# RoboRoach.net
KiCad netlist of a schematic drawn in EAGLE
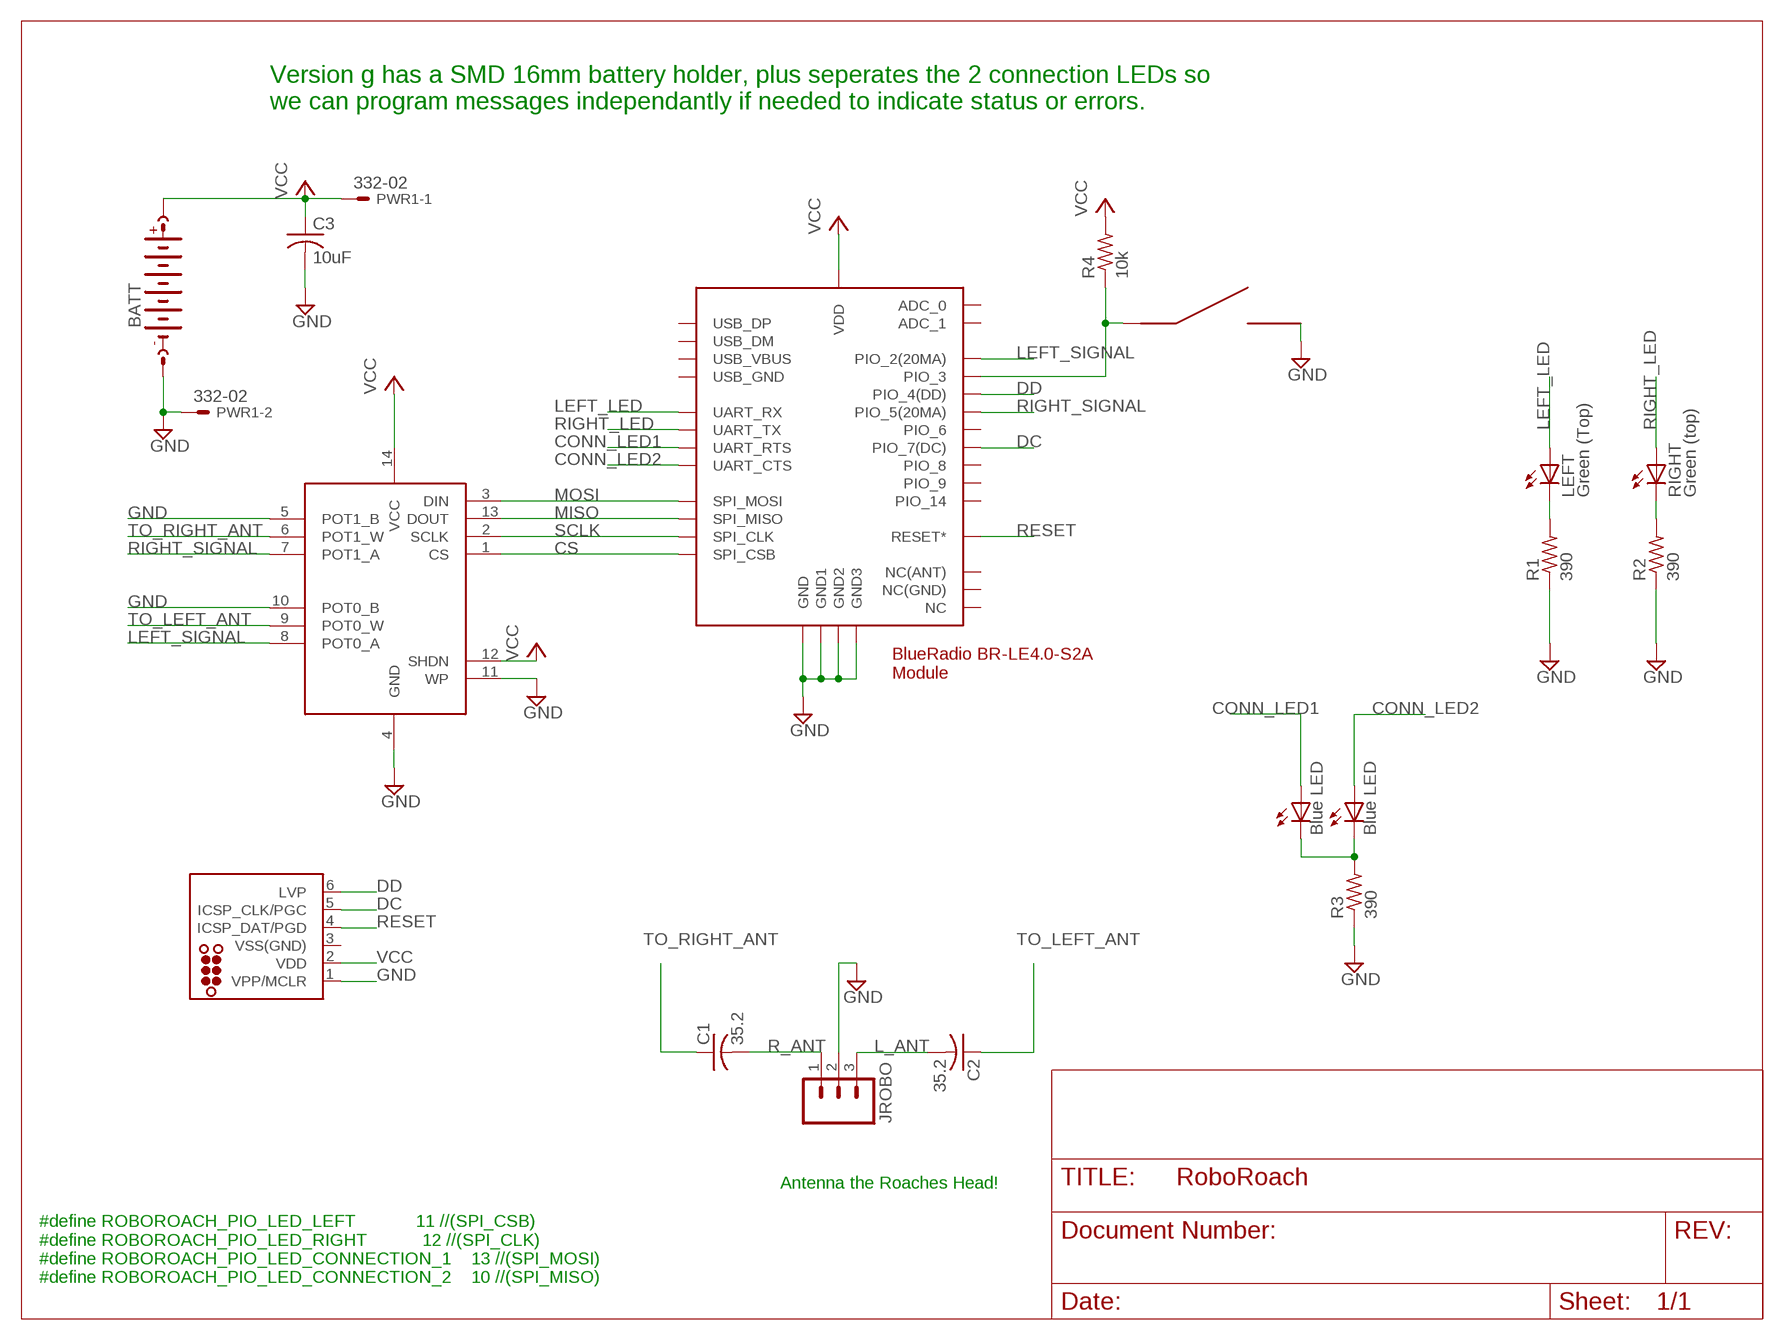
[diagram p0: schematic, sheet 1]

(export (version "E")
  (design (tool "Eeschema 10.0.6"))
  (components
    (comp (ref "BATT")
      (value "BATTERY-16MMSMD")
      (footprint "eagle-import:16M_BATT_SMD")
      (libsource (lib "eagle-import") (part "BATTERY-16MMSMD"))
    )
    (comp (ref "C1")
      (value "35.2")
      (footprint "eagle-import:C0805")
      (libsource (lib "eagle-import") (part "C-USC0805"))
    )
    (comp (ref "C2")
      (value "35.2")
      (footprint "eagle-import:C0805")
      (libsource (lib "eagle-import") (part "C-USC0805"))
    )
    (comp (ref "C3")
      (value "10uF")
      (footprint "eagle-import:C0805")
      (libsource (lib "eagle-import") (part "C-USC0805"))
    )
    (comp (ref "CONNECTION")
      (value "Blue LED")
      (footprint "eagle-import:CHIPLED_1206")
      (libsource (lib "eagle-import") (part "LEDCHIPLED_1206"))
    )
    (comp (ref "CONNECTION1")
      (value "Blue LED")
      (footprint "eagle-import:CHIPLED_1206")
      (libsource (lib "eagle-import") (part "LEDCHIPLED_1206"))
    )
    (comp (ref "IC1")
      (value "BR-LE4.0-S2")
      (footprint "eagle-import:BR-LE4.0-X2A")
      (libsource (lib "eagle-import") (part "BR-LE4.0-S2"))
    )
    (comp (ref "J1")
      (value "TC2030-MCP-NL")
      (footprint "eagle-import:TC2030-MCP-NL")
      (libsource (lib "eagle-import") (part "TC2030-MCP-NL"))
    )
    (comp (ref "JROBO")
      (value "M03PTH")
      (footprint "eagle-import:1X03")
      (libsource (lib "eagle-import") (part "M03PTH"))
    )
    (comp (ref "LEFT")
      (value "Green (Top)")
      (footprint "eagle-import:CHIPLED_1206")
      (libsource (lib "eagle-import") (part "LEDCHIPLED_1206"))
    )
    (comp (ref "POT")
      (value "MCP4251")
      (footprint "eagle-import:TSSOP14")
      (libsource (lib "eagle-import") (part "MCP4251"))
    )
    (comp (ref "PWR1")
      (value "332-02")
      (footprint "eagle-import:332-02")
      (libsource (lib "eagle-import") (part "332-02"))
    )
    (comp (ref "R1")
      (value "390")
      (footprint "eagle-import:R0805")
      (libsource (lib "eagle-import") (part "R-US_R0805"))
    )
    (comp (ref "R2")
      (value "390")
      (footprint "eagle-import:R0805")
      (libsource (lib "eagle-import") (part "R-US_R0805"))
    )
    (comp (ref "R3")
      (value "390")
      (footprint "eagle-import:R0805")
      (libsource (lib "eagle-import") (part "R-US_R0805"))
    )
    (comp (ref "R4")
      (value "10k")
      (footprint "eagle-import:R0805")
      (libsource (lib "eagle-import") (part "R-US_R0805"))
    )
    (comp (ref "RIGHT")
      (value "Green (top)")
      (footprint "eagle-import:CHIPLED_1206")
      (libsource (lib "eagle-import") (part "LEDCHIPLED_1206"))
    )
    (comp (ref "U$2")
      (value "B3U-1000X")
      (footprint "eagle-import:B3U")
      (libsource (lib "eagle-import") (part "B3U-1000X"))
    )
  )
  (nets
    (net (code "1") (name "/CONN_LED1") (class "Default")
      (node (ref "CONNECTION1") (pin "A") (pinfunction "A_A") (pintype "passive"))
      (node (ref "IC1") (pin "P$12") (pinfunction "UART_RTS_P$12") (pintype "bidirectional"))
    )
    (net (code "2") (name "/CONN_LED2") (class "Default")
      (node (ref "CONNECTION") (pin "A") (pinfunction "A_A") (pintype "passive"))
      (node (ref "IC1") (pin "P$11") (pinfunction "UART_CTS_P$11") (pintype "bidirectional"))
    )
    (net (code "3") (name "/CS") (class "Default")
      (node (ref "IC1") (pin "P$6") (pinfunction "SPI_CSB_P$6") (pintype "bidirectional"))
      (node (ref "POT") (pin "1") (pinfunction "CS_1") (pintype "input"))
    )
    (net (code "4") (name "/DC") (class "Default")
      (node (ref "IC1") (pin "P$29") (pinfunction "PIO_7(DC)_P$29") (pintype "bidirectional"))
      (node (ref "J1") (pin "5") (pinfunction "ICSP_CLK/PGC_5") (pintype "output"))
    )
    (net (code "5") (name "/DD") (class "Default")
      (node (ref "IC1") (pin "P$28") (pinfunction "PIO_4(DD)_P$28") (pintype "bidirectional"))
      (node (ref "J1") (pin "6") (pinfunction "LVP_6") (pintype "bidirectional"))
    )
    (net (code "6") (name "/LEFT_LED") (class "Default")
      (node (ref "IC1") (pin "P$14") (pinfunction "UART_RX_P$14") (pintype "bidirectional"))
      (node (ref "LEFT") (pin "A") (pinfunction "A_A") (pintype "passive"))
    )
    (net (code "7") (name "/LEFT_SIGNAL") (class "Default")
      (node (ref "IC1") (pin "P$23") (pinfunction "PIO_2(20MA)_P$23") (pintype "bidirectional"))
      (node (ref "POT") (pin "8") (pinfunction "POT0_A_8") (pintype "bidirectional"))
    )
    (net (code "8") (name "/L_ANT") (class "Default")
      (node (ref "C2") (pin "2") (pinfunction "2_2") (pintype "passive"))
      (node (ref "JROBO") (pin "3") (pinfunction "3_3") (pintype "passive"))
    )
    (net (code "9") (name "/MISO") (class "Default")
      (node (ref "IC1") (pin "P$5") (pinfunction "SPI_MISO_P$5") (pintype "bidirectional"))
      (node (ref "POT") (pin "13") (pinfunction "DOUT_13") (pintype "output"))
    )
    (net (code "10") (name "/MOSI") (class "Default")
      (node (ref "IC1") (pin "P$8") (pinfunction "SPI_MOSI_P$8") (pintype "bidirectional"))
      (node (ref "POT") (pin "3") (pinfunction "DIN_3") (pintype "input"))
    )
    (net (code "11") (name "/RESET") (class "Default")
      (node (ref "IC1") (pin "P$3") (pinfunction "RESET*_P$3") (pintype "bidirectional"))
      (node (ref "J1") (pin "4") (pinfunction "ICSP_DAT/PGD_4") (pintype "bidirectional"))
    )
    (net (code "12") (name "/RIGHT_LED") (class "Default")
      (node (ref "IC1") (pin "P$13") (pinfunction "UART_TX_P$13") (pintype "bidirectional"))
      (node (ref "RIGHT") (pin "A") (pinfunction "A_A") (pintype "passive"))
    )
    (net (code "13") (name "/RIGHT_SIGNAL") (class "Default")
      (node (ref "IC1") (pin "P$24") (pinfunction "PIO_5(20MA)_P$24") (pintype "bidirectional"))
      (node (ref "POT") (pin "7") (pinfunction "POT1_A_7") (pintype "bidirectional"))
    )
    (net (code "14") (name "/R_ANT") (class "Default")
      (node (ref "C1") (pin "2") (pinfunction "2_2") (pintype "passive"))
      (node (ref "JROBO") (pin "1") (pinfunction "1_1") (pintype "passive"))
    )
    (net (code "15") (name "/SCLK") (class "Default")
      (node (ref "IC1") (pin "P$7") (pinfunction "SPI_CLK_P$7") (pintype "bidirectional"))
      (node (ref "POT") (pin "2") (pinfunction "SCLK_2") (pintype "input"))
    )
    (net (code "16") (name "/TO_LEFT_ANT") (class "Default")
      (node (ref "C2") (pin "1") (pinfunction "1_1") (pintype "passive"))
      (node (ref "POT") (pin "9") (pinfunction "POT0_W_9") (pintype "bidirectional"))
    )
    (net (code "17") (name "/TO_RIGHT_ANT") (class "Default")
      (node (ref "C1") (pin "1") (pinfunction "1_1") (pintype "passive"))
      (node (ref "POT") (pin "6") (pinfunction "POT1_W_6") (pintype "bidirectional"))
    )
    (net (code "18") (name "/VSS(GND)") (class "Default")
      (node (ref "J1") (pin "3") (pinfunction "VSS(GND)_3") (pintype "power_in"))
    )
    (net (code "19") (name "GND") (class "Default")
      (node (ref "BATT") (pin "NEG") (pinfunction "-_NEG") (pintype "passive"))
      (node (ref "C3") (pin "2") (pinfunction "2_2") (pintype "passive"))
      (node (ref "IC1") (pin "P$1") (pinfunction "GND_P$1") (pintype "power_in"))
      (node (ref "IC1") (pin "P$10") (pinfunction "GND1_P$10") (pintype "power_in"))
      (node (ref "IC1") (pin "P$20") (pinfunction "GND2_P$20") (pintype "power_in"))
      (node (ref "IC1") (pin "P$30") (pinfunction "GND3_P$30") (pintype "power_in"))
      (node (ref "J1") (pin "1") (pinfunction "VPP/MCLR_1") (pintype "passive"))
      (node (ref "JROBO") (pin "2") (pinfunction "2_2") (pintype "passive"))
      (node (ref "POT") (pin "10") (pinfunction "POT0_B_10") (pintype "bidirectional"))
      (node (ref "POT") (pin "11") (pinfunction "WP_11") (pintype "input"))
      (node (ref "POT") (pin "4") (pinfunction "GND_4") (pintype "power_in"))
      (node (ref "POT") (pin "5") (pinfunction "POT1_B_5") (pintype "bidirectional"))
      (node (ref "PWR1") (pin "2") (pinfunction "S_2") (pintype "passive"))
      (node (ref "R1") (pin "1") (pinfunction "1_1") (pintype "passive"))
      (node (ref "R2") (pin "1") (pinfunction "1_1") (pintype "passive"))
      (node (ref "R3") (pin "1") (pinfunction "1_1") (pintype "passive"))
      (node (ref "U$2") (pin "PAD2") (pinfunction "P$2_PAD2") (pintype "bidirectional"))
    )
    (net (code "20") (name "Net-(CONNECTION-PadC)") (class "Default")
      (node (ref "CONNECTION") (pin "C") (pinfunction "C_C") (pintype "passive"))
      (node (ref "CONNECTION1") (pin "C") (pinfunction "C_C") (pintype "passive"))
      (node (ref "R3") (pin "2") (pinfunction "2_2") (pintype "passive"))
    )
    (net (code "21") (name "Net-(IC1-PIO_3)") (class "Default")
      (node (ref "IC1") (pin "P$26") (pinfunction "PIO_3_P$26") (pintype "bidirectional"))
      (node (ref "R4") (pin "1") (pinfunction "1_1") (pintype "passive"))
      (node (ref "U$2") (pin "PAD1") (pinfunction "P$1_PAD1") (pintype "bidirectional"))
    )
    (net (code "22") (name "Net-(LEFT-PadC)") (class "Default")
      (node (ref "LEFT") (pin "C") (pinfunction "C_C") (pintype "passive"))
      (node (ref "R1") (pin "2") (pinfunction "2_2") (pintype "passive"))
    )
    (net (code "23") (name "Net-(R2-Pad2)") (class "Default")
      (node (ref "R2") (pin "2") (pinfunction "2_2") (pintype "passive"))
      (node (ref "RIGHT") (pin "C") (pinfunction "C_C") (pintype "passive"))
    )
    (net (code "24") (name "VCC") (class "Default")
      (node (ref "BATT") (pin "POS1") (pinfunction "+_POS1") (pintype "passive"))
      (node (ref "BATT") (pin "POS2") (pinfunction "+_POS2") (pintype "passive"))
      (node (ref "C3") (pin "1") (pinfunction "1_1") (pintype "passive"))
      (node (ref "IC1") (pin "P$9") (pinfunction "VDD_P$9") (pintype "power_in"))
      (node (ref "J1") (pin "2") (pinfunction "VDD_2") (pintype "power_in"))
      (node (ref "POT") (pin "12") (pinfunction "SHDN_12") (pintype "input"))
      (node (ref "POT") (pin "14") (pinfunction "VCC_14") (pintype "power_in"))
      (node (ref "PWR1") (pin "1") (pinfunction "S_1") (pintype "passive"))
      (node (ref "R4") (pin "2") (pinfunction "2_2") (pintype "passive"))
    )
    (net (code "25") (name "unconnected-(IC1-ADC_0-PadP$21)") (class "Default")
      (node (ref "IC1") (pin "P$21") (pinfunction "ADC_0_P$21") (pintype "bidirectional"))
    )
    (net (code "26") (name "unconnected-(IC1-ADC_1-PadP$4)") (class "Default")
      (node (ref "IC1") (pin "P$4") (pinfunction "ADC_1_P$4") (pintype "bidirectional"))
    )
    (net (code "27") (name "unconnected-(IC1-NC(ANT)-PadP$31)") (class "Default")
      (node (ref "IC1") (pin "P$31") (pinfunction "NC(ANT)_P$31") (pintype "bidirectional"))
    )
    (net (code "28") (name "unconnected-(IC1-NC(GND)-PadP$32)") (class "Default")
      (node (ref "IC1") (pin "P$32") (pinfunction "NC(GND)_P$32") (pintype "bidirectional"))
    )
    (net (code "29") (name "unconnected-(IC1-NC-PadP$2)") (class "Default")
      (node (ref "IC1") (pin "P$2") (pinfunction "NC_P$2") (pintype "bidirectional"))
    )
    (net (code "30") (name "unconnected-(IC1-PIO_6-PadP$25)") (class "Default")
      (node (ref "IC1") (pin "P$25") (pinfunction "PIO_6_P$25") (pintype "bidirectional"))
    )
    (net (code "31") (name "unconnected-(IC1-PIO_8-PadP$27)") (class "Default")
      (node (ref "IC1") (pin "P$27") (pinfunction "PIO_8_P$27") (pintype "bidirectional"))
    )
    (net (code "32") (name "unconnected-(IC1-PIO_9-PadP$22)") (class "Default")
      (node (ref "IC1") (pin "P$22") (pinfunction "PIO_9_P$22") (pintype "bidirectional"))
    )
    (net (code "33") (name "unconnected-(IC1-PIO_14-PadP$19)") (class "Default")
      (node (ref "IC1") (pin "P$19") (pinfunction "PIO_14_P$19") (pintype "bidirectional"))
    )
    (net (code "34") (name "unconnected-(IC1-USB_DM-PadP$18)") (class "Default")
      (node (ref "IC1") (pin "P$18") (pinfunction "USB_DM_P$18") (pintype "bidirectional"))
    )
    (net (code "35") (name "unconnected-(IC1-USB_DP-PadP$17)") (class "Default")
      (node (ref "IC1") (pin "P$17") (pinfunction "USB_DP_P$17") (pintype "bidirectional"))
    )
    (net (code "36") (name "unconnected-(IC1-USB_GND-PadP$16)") (class "Default")
      (node (ref "IC1") (pin "P$16") (pinfunction "USB_GND_P$16") (pintype "bidirectional"))
    )
    (net (code "37") (name "unconnected-(IC1-USB_VBUS-PadP$15)") (class "Default")
      (node (ref "IC1") (pin "P$15") (pinfunction "USB_VBUS_P$15") (pintype "bidirectional"))
    )
  )
)
